# SparkFun_GPS_Evaluation_Board_GP-2106.net
KiCad netlist of a schematic drawn in EAGLE
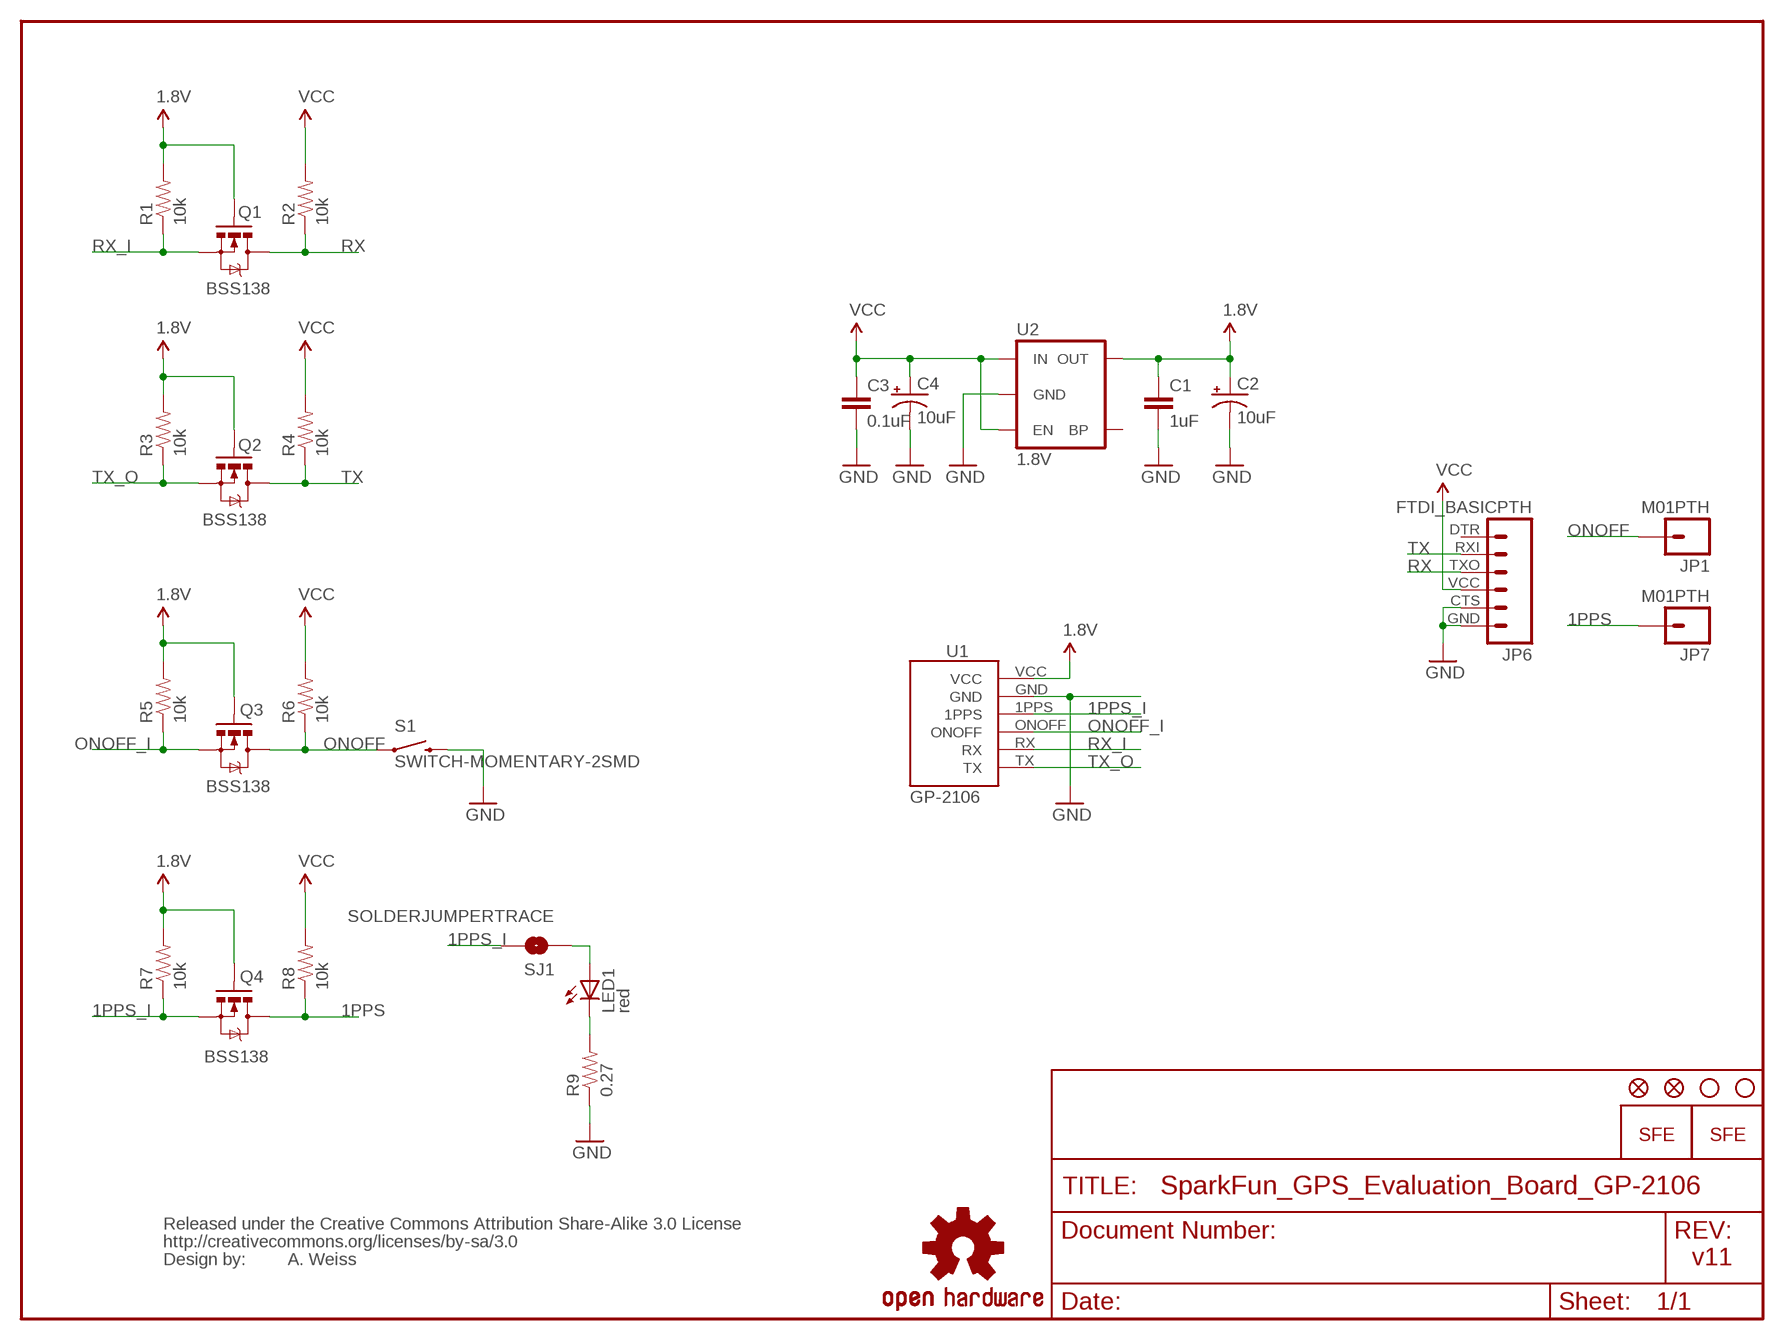
[diagram p0: schematic, sheet 1]

(export (version "E")
  (design (tool "Eeschema 10.0.6"))
  (components
    (comp (ref "C1")
      (value "1uF")
      (footprint "eagle-import:0402-CAP")
      (libsource (lib "eagle-import") (part "CAP0402-CAP"))
    )
    (comp (ref "C2")
      (value "10uF")
      (footprint "eagle-import:EIA3216")
      (libsource (lib "eagle-import") (part "CAP_POL1206"))
    )
    (comp (ref "C3")
      (value "0.1uF")
      (footprint "eagle-import:0402-CAP")
      (libsource (lib "eagle-import") (part "CAP0402-CAP"))
    )
    (comp (ref "C4")
      (value "10uF")
      (footprint "eagle-import:EIA3216")
      (libsource (lib "eagle-import") (part "CAP_POL1206"))
    )
    (comp (ref "JP1")
      (value "M01PTH")
      (footprint "eagle-import:1X01")
      (libsource (lib "eagle-import") (part "M01PTH"))
    )
    (comp (ref "JP2")
      (value "STAND-OFF")
      (footprint "eagle-import:STAND-OFF")
      (libsource (lib "eagle-import") (part "STAND-OFF"))
    )
    (comp (ref "JP3")
      (value "STAND-OFF")
      (footprint "eagle-import:STAND-OFF")
      (libsource (lib "eagle-import") (part "STAND-OFF"))
    )
    (comp (ref "JP4")
      (value "LOGO-SFESK")
      (footprint "eagle-import:SFE-LOGO-FLAME")
      (libsource (lib "eagle-import") (part "LOGO-SFESK"))
    )
    (comp (ref "JP5")
      (value "LOGO-SFENEW")
      (footprint "eagle-import:SFE-NEW-WEBLOGO")
      (libsource (lib "eagle-import") (part "LOGO-SFENEW"))
    )
    (comp (ref "JP6")
      (value "FTDI_BASICPTH")
      (footprint "eagle-import:FTDI_BASIC")
      (libsource (lib "eagle-import") (part "FTDI_BASICPTH"))
    )
    (comp (ref "JP7")
      (value "M01PTH")
      (footprint "eagle-import:1X01")
      (libsource (lib "eagle-import") (part "M01PTH"))
    )
    (comp (ref "JP8")
      (value "FIDUCIALUFIDUCIAL")
      (footprint "eagle-import:MICRO-FIDUCIAL")
      (libsource (lib "eagle-import") (part "FIDUCIALUFIDUCIAL"))
    )
    (comp (ref "JP9")
      (value "FIDUCIALUFIDUCIAL")
      (footprint "eagle-import:MICRO-FIDUCIAL")
      (libsource (lib "eagle-import") (part "FIDUCIALUFIDUCIAL"))
    )
    (comp (ref "LED1")
      (value "red")
      (footprint "eagle-import:LED-0603")
      (libsource (lib "eagle-import") (part "LED0603"))
    )
    (comp (ref "Q1")
      (value "MOSFET-NCHANNELSMD")
      (footprint "eagle-import:SOT23-3")
      (libsource (lib "eagle-import") (part "MOSFET-NCHANNELSMD"))
    )
    (comp (ref "Q2")
      (value "MOSFET-NCHANNELSMD")
      (footprint "eagle-import:SOT23-3")
      (libsource (lib "eagle-import") (part "MOSFET-NCHANNELSMD"))
    )
    (comp (ref "Q3")
      (value "MOSFET-NCHANNELSMD")
      (footprint "eagle-import:SOT23-3")
      (libsource (lib "eagle-import") (part "MOSFET-NCHANNELSMD"))
    )
    (comp (ref "Q4")
      (value "MOSFET-NCHANNELSMD")
      (footprint "eagle-import:SOT23-3")
      (libsource (lib "eagle-import") (part "MOSFET-NCHANNELSMD"))
    )
    (comp (ref "R1")
      (value "10k")
      (footprint "eagle-import:0402-RES")
      (libsource (lib "eagle-import") (part "RESISTOR0402-RES"))
    )
    (comp (ref "R2")
      (value "10k")
      (footprint "eagle-import:0402-RES")
      (libsource (lib "eagle-import") (part "RESISTOR0402-RES"))
    )
    (comp (ref "R3")
      (value "10k")
      (footprint "eagle-import:0402-RES")
      (libsource (lib "eagle-import") (part "RESISTOR0402-RES"))
    )
    (comp (ref "R4")
      (value "10k")
      (footprint "eagle-import:0402-RES")
      (libsource (lib "eagle-import") (part "RESISTOR0402-RES"))
    )
    (comp (ref "R5")
      (value "10k")
      (footprint "eagle-import:0402-RES")
      (libsource (lib "eagle-import") (part "RESISTOR0402-RES"))
    )
    (comp (ref "R6")
      (value "10k")
      (footprint "eagle-import:0402-RES")
      (libsource (lib "eagle-import") (part "RESISTOR0402-RES"))
    )
    (comp (ref "R7")
      (value "10k")
      (footprint "eagle-import:0402-RES")
      (libsource (lib "eagle-import") (part "RESISTOR0402-RES"))
    )
    (comp (ref "R8")
      (value "10k")
      (footprint "eagle-import:0402-RES")
      (libsource (lib "eagle-import") (part "RESISTOR0402-RES"))
    )
    (comp (ref "R9")
      (value "0.27")
      (footprint "eagle-import:0402-RES")
      (libsource (lib "eagle-import") (part "RESISTOR0402-RES"))
    )
    (comp (ref "S1")
      (value "SWITCH-MOMENTARY-2SMD")
      (footprint "eagle-import:TACTILE_SWITCH_SMD")
      (libsource (lib "eagle-import") (part "SWITCH-MOMENTARY-2SMD"))
    )
    (comp (ref "SJ1")
      (value "SOLDERJUMPERTRACE")
      (footprint "eagle-import:SJ_2S-TRACE")
      (libsource (lib "eagle-import") (part "SOLDERJUMPERTRACE"))
    )
    (comp (ref "U$7")
      (value "OSHW-LOGOS")
      (footprint "eagle-import:OSHW-LOGO-S")
      (libsource (lib "eagle-import") (part "OSHW-LOGOS"))
    )
    (comp (ref "U$8")
      (value "CREATIVE_COMMONS")
      (footprint "eagle-import:CREATIVE_COMMONS")
      (libsource (lib "eagle-import") (part "CREATIVE_COMMONS"))
    )
    (comp (ref "U1")
      (value "GP-2106")
      (footprint "eagle-import:GP-2106")
      (libsource (lib "eagle-import") (part "GP-2106"))
    )
    (comp (ref "U2")
      (value "V_REG_LDOSMD2")
      (footprint "eagle-import:SC70")
      (libsource (lib "eagle-import") (part "V_REG_LDOSMD2"))
    )
  )
  (nets
    (net (code "1") (name "/1PPS") (class "Default")
      (node (ref "JP7") (pin "1") (pinfunction "1_1") (pintype "passive"))
      (node (ref "Q4") (pin "3") (pinfunction "D_3") (pintype "passive"))
      (node (ref "R8") (pin "1") (pinfunction "1_1") (pintype "passive"))
    )
    (net (code "2") (name "/1PPS_I") (class "Default")
      (node (ref "Q4") (pin "2") (pinfunction "S_2") (pintype "passive"))
      (node (ref "R7") (pin "1") (pinfunction "1_1") (pintype "passive"))
      (node (ref "SJ1") (pin "2") (pinfunction "2_2") (pintype "passive"))
      (node (ref "U1") (pin "1PPS") (pinfunction "1PPS_1PPS") (pintype "bidirectional"))
    )
    (net (code "3") (name "/ONOFF") (class "Default")
      (node (ref "JP1") (pin "1") (pinfunction "1_1") (pintype "passive"))
      (node (ref "Q3") (pin "3") (pinfunction "D_3") (pintype "passive"))
      (node (ref "R6") (pin "1") (pinfunction "1_1") (pintype "passive"))
      (node (ref "S1") (pin "1") (pinfunction "1_1") (pintype "passive"))
    )
    (net (code "4") (name "/ONOFF_I") (class "Default")
      (node (ref "Q3") (pin "2") (pinfunction "S_2") (pintype "passive"))
      (node (ref "R5") (pin "1") (pinfunction "1_1") (pintype "passive"))
      (node (ref "U1") (pin "ONOFF") (pinfunction "ONOFF_ONOFF") (pintype "bidirectional"))
    )
    (net (code "5") (name "/RX") (class "Default")
      (node (ref "JP6") (pin "TXO") (pinfunction "3_TXO") (pintype "passive"))
      (node (ref "Q1") (pin "3") (pinfunction "D_3") (pintype "passive"))
      (node (ref "R2") (pin "1") (pinfunction "1_1") (pintype "passive"))
    )
    (net (code "6") (name "/RX_I") (class "Default")
      (node (ref "Q1") (pin "2") (pinfunction "S_2") (pintype "passive"))
      (node (ref "R1") (pin "1") (pinfunction "1_1") (pintype "passive"))
      (node (ref "U1") (pin "RX") (pinfunction "RX_RX") (pintype "bidirectional"))
    )
    (net (code "7") (name "/TX") (class "Default")
      (node (ref "JP6") (pin "RXI") (pinfunction "2_RXI") (pintype "passive"))
      (node (ref "Q2") (pin "3") (pinfunction "D_3") (pintype "passive"))
      (node (ref "R4") (pin "1") (pinfunction "1_1") (pintype "passive"))
    )
    (net (code "8") (name "/TX_O") (class "Default")
      (node (ref "Q2") (pin "2") (pinfunction "S_2") (pintype "passive"))
      (node (ref "R3") (pin "1") (pinfunction "1_1") (pintype "passive"))
      (node (ref "U1") (pin "TX") (pinfunction "TX_TX") (pintype "bidirectional"))
    )
    (net (code "9") (name "1.8V") (class "Default")
      (node (ref "C1") (pin "1") (pinfunction "1_1") (pintype "passive"))
      (node (ref "C2") (pin "A") (pinfunction "+_A") (pintype "passive"))
      (node (ref "Q1") (pin "1") (pinfunction "G_1") (pintype "passive"))
      (node (ref "Q2") (pin "1") (pinfunction "G_1") (pintype "passive"))
      (node (ref "Q3") (pin "1") (pinfunction "G_1") (pintype "passive"))
      (node (ref "Q4") (pin "1") (pinfunction "G_1") (pintype "passive"))
      (node (ref "R1") (pin "2") (pinfunction "2_2") (pintype "passive"))
      (node (ref "R3") (pin "2") (pinfunction "2_2") (pintype "passive"))
      (node (ref "R5") (pin "2") (pinfunction "2_2") (pintype "passive"))
      (node (ref "R7") (pin "2") (pinfunction "2_2") (pintype "passive"))
      (node (ref "U1") (pin "VCC") (pinfunction "VCC_VCC") (pintype "bidirectional"))
      (node (ref "U2") (pin "5") (pinfunction "OUT_5") (pintype "passive"))
    )
    (net (code "10") (name "GND") (class "Default")
      (node (ref "C1") (pin "2") (pinfunction "2_2") (pintype "passive"))
      (node (ref "C2") (pin "C") (pinfunction "-_C") (pintype "passive"))
      (node (ref "C3") (pin "2") (pinfunction "2_2") (pintype "passive"))
      (node (ref "C4") (pin "C") (pinfunction "-_C") (pintype "passive"))
      (node (ref "JP6") (pin "CTS") (pinfunction "5_CTS") (pintype "passive"))
      (node (ref "JP6") (pin "GND") (pinfunction "6_GND") (pintype "passive"))
      (node (ref "R9") (pin "1") (pinfunction "1_1") (pintype "passive"))
      (node (ref "S1") (pin "3") (pinfunction "2_3") (pintype "passive"))
      (node (ref "U1") (pin "GND") (pinfunction "GND_GND") (pintype "bidirectional"))
      (node (ref "U2") (pin "2") (pinfunction "GND_2") (pintype "input"))
    )
    (net (code "11") (name "Net-(LED1-PadA)") (class "Default")
      (node (ref "LED1") (pin "A") (pinfunction "A_A") (pintype "passive"))
      (node (ref "SJ1") (pin "1") (pinfunction "1_1") (pintype "passive"))
    )
    (net (code "12") (name "Net-(LED1-PadC)") (class "Default")
      (node (ref "LED1") (pin "C") (pinfunction "C_C") (pintype "passive"))
      (node (ref "R9") (pin "2") (pinfunction "2_2") (pintype "passive"))
    )
    (net (code "13") (name "VCC") (class "Default")
      (node (ref "C3") (pin "1") (pinfunction "1_1") (pintype "passive"))
      (node (ref "C4") (pin "A") (pinfunction "+_A") (pintype "passive"))
      (node (ref "JP6") (pin "VCC") (pinfunction "4_VCC") (pintype "passive"))
      (node (ref "R2") (pin "2") (pinfunction "2_2") (pintype "passive"))
      (node (ref "R4") (pin "2") (pinfunction "2_2") (pintype "passive"))
      (node (ref "R6") (pin "2") (pinfunction "2_2") (pintype "passive"))
      (node (ref "R8") (pin "2") (pinfunction "2_2") (pintype "passive"))
      (node (ref "U2") (pin "1") (pinfunction "IN_1") (pintype "input"))
      (node (ref "U2") (pin "3") (pinfunction "EN_3") (pintype "input"))
    )
    (net (code "14") (name "unconnected-(JP6-1-PadDTR)") (class "Default")
      (node (ref "JP6") (pin "DTR") (pinfunction "1_DTR") (pintype "passive"))
    )
    (net (code "15") (name "unconnected-(U2-BP-Pad4)") (class "Default")
      (node (ref "U2") (pin "4") (pinfunction "BP_4") (pintype "input"))
    )
  )
)
